# alpha_board_05a.net
KiCad netlist of a schematic drawn in EAGLE
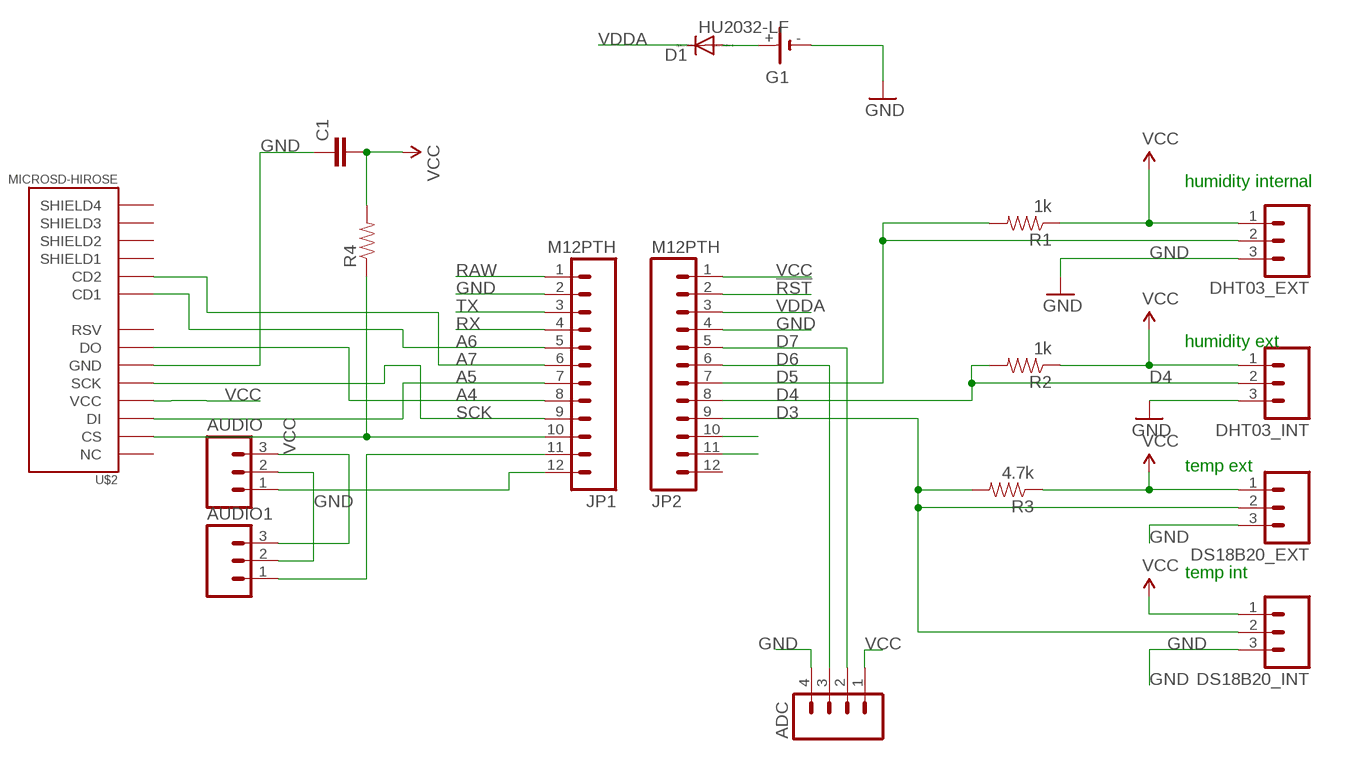
[diagram p0: schematic, sheet 1]

(export (version "E")
  (design (tool "Eeschema 10.0.6"))
  (components
    (comp (ref "ADC")
      (value "M04LOCK_LONGPADS")
      (footprint "eagle-import:1X04_LOCK_LONGPADS")
      (libsource (lib "eagle-import") (part "M04LOCK_LONGPADS"))
    )
    (comp (ref "AUDIO")
      (value "M03LOCK")
      (footprint "eagle-import:1X03_LOCK")
      (libsource (lib "eagle-import") (part "M03LOCK"))
    )
    (comp (ref "AUDIO1")
      (value "M03LOCK")
      (footprint "eagle-import:1X03_LOCK")
      (libsource (lib "eagle-import") (part "M03LOCK"))
    )
    (comp (ref "C1")
      (value "CAP1206")
      (footprint "eagle-import:1206")
      (libsource (lib "eagle-import") (part "CAP1206"))
    )
    (comp (ref "D1")
      (value "DIODE-SOD323-W")
      (footprint "eagle-import:SOD323-W")
      (libsource (lib "eagle-import") (part "DIODE-SOD323-W"))
    )
    (comp (ref "DHT03_EXT")
      (value "M03LOCK")
      (footprint "eagle-import:1X03_LOCK")
      (libsource (lib "eagle-import") (part "M03LOCK"))
    )
    (comp (ref "DHT03_INT")
      (value "M03LOCK")
      (footprint "eagle-import:1X03_LOCK")
      (libsource (lib "eagle-import") (part "M03LOCK"))
    )
    (comp (ref "DS18B20_EXT")
      (value "M03LOCK")
      (footprint "eagle-import:1X03_LOCK")
      (libsource (lib "eagle-import") (part "M03LOCK"))
    )
    (comp (ref "DS18B20_INT")
      (value "M03LOCK")
      (footprint "eagle-import:1X03_LOCK")
      (libsource (lib "eagle-import") (part "M03LOCK"))
    )
    (comp (ref "G1")
      (value "HU2032-LF")
      (footprint "eagle-import:HU2032-LF")
      (libsource (lib "eagle-import") (part "HU2032-LF"))
    )
    (comp (ref "JP1")
      (value "M12PTH")
      (footprint "eagle-import:1X12-SMALL-PADS")
      (libsource (lib "eagle-import") (part "M12PTH"))
    )
    (comp (ref "JP2")
      (value "M12PTH")
      (footprint "eagle-import:1X12-SMALL-PADS")
      (libsource (lib "eagle-import") (part "M12PTH"))
    )
    (comp (ref "R1")
      (value "1k")
      (footprint "eagle-import:1206")
      (libsource (lib "eagle-import") (part "RESISTOR1206"))
    )
    (comp (ref "R2")
      (value "1k")
      (footprint "eagle-import:1206")
      (libsource (lib "eagle-import") (part "RESISTOR1206"))
    )
    (comp (ref "R3")
      (value "4.7k")
      (footprint "eagle-import:1206")
      (libsource (lib "eagle-import") (part "RESISTOR1206"))
    )
    (comp (ref "R4")
      (value "RESISTOR1206")
      (footprint "eagle-import:1206")
      (libsource (lib "eagle-import") (part "RESISTOR1206"))
    )
    (comp (ref "U$2")
      (value "MICROSD-HIROSE")
      (footprint "eagle-import:MICROSD_HOLDER-HIROSE-DM3AT")
      (libsource (lib "eagle-import") (part "MICROSD-HIROSE"))
    )
  )
  (nets
    (net (code "1") (name "/A4") (class "Default")
      (node (ref "JP1") (pin "8") (pinfunction "8_8") (pintype "passive"))
      (node (ref "U$2") (pin "DAT0") (pinfunction "DO_DAT0") (pintype "bidirectional"))
    )
    (net (code "2") (name "/A5") (class "Default")
      (node (ref "JP1") (pin "7") (pinfunction "7_7") (pintype "passive"))
      (node (ref "U$2") (pin "CMD") (pinfunction "DI_CMD") (pintype "bidirectional"))
    )
    (net (code "3") (name "/A6") (class "Default")
      (node (ref "JP1") (pin "5") (pinfunction "5_5") (pintype "passive"))
      (node (ref "U$2") (pin "CD1") (pinfunction "CD1_CD1") (pintype "bidirectional"))
    )
    (net (code "4") (name "/A7") (class "Default")
      (node (ref "JP1") (pin "6") (pinfunction "6_6") (pintype "passive"))
      (node (ref "U$2") (pin "CD2") (pinfunction "CD2_CD2") (pintype "bidirectional"))
    )
    (net (code "5") (name "/D3") (class "Default")
      (node (ref "DS18B20_EXT") (pin "2") (pinfunction "2_2") (pintype "passive"))
      (node (ref "DS18B20_INT") (pin "2") (pinfunction "2_2") (pintype "passive"))
      (node (ref "JP2") (pin "9") (pinfunction "9_9") (pintype "passive"))
      (node (ref "R3") (pin "2") (pinfunction "2_2") (pintype "passive"))
    )
    (net (code "6") (name "/D4") (class "Default")
      (node (ref "DHT03_INT") (pin "2") (pinfunction "2_2") (pintype "passive"))
      (node (ref "JP2") (pin "8") (pinfunction "8_8") (pintype "passive"))
      (node (ref "R2") (pin "2") (pinfunction "2_2") (pintype "passive"))
    )
    (net (code "7") (name "/D5") (class "Default")
      (node (ref "DHT03_EXT") (pin "2") (pinfunction "2_2") (pintype "passive"))
      (node (ref "JP2") (pin "7") (pinfunction "7_7") (pintype "passive"))
      (node (ref "R1") (pin "2") (pinfunction "2_2") (pintype "passive"))
    )
    (net (code "8") (name "/D6") (class "Default")
      (node (ref "ADC") (pin "3") (pinfunction "3_3") (pintype "passive"))
      (node (ref "JP2") (pin "6") (pinfunction "6_6") (pintype "passive"))
    )
    (net (code "9") (name "/D7") (class "Default")
      (node (ref "ADC") (pin "2") (pinfunction "2_2") (pintype "passive"))
      (node (ref "JP2") (pin "5") (pinfunction "5_5") (pintype "passive"))
    )
    (net (code "10") (name "/RAW") (class "Default")
      (node (ref "JP1") (pin "1") (pinfunction "1_1") (pintype "passive"))
    )
    (net (code "11") (name "/RX") (class "Default")
      (node (ref "JP1") (pin "4") (pinfunction "4_4") (pintype "passive"))
    )
    (net (code "12") (name "/SCK") (class "Default")
      (node (ref "JP1") (pin "9") (pinfunction "9_9") (pintype "passive"))
      (node (ref "U$2") (pin "CLK") (pinfunction "SCK_CLK") (pintype "bidirectional"))
    )
    (net (code "13") (name "/TX") (class "Default")
      (node (ref "JP1") (pin "3") (pinfunction "3_3") (pintype "passive"))
    )
    (net (code "14") (name "/VDDA") (class "Default")
      (node (ref "D1") (pin "C") (pinfunction "C_C") (pintype "passive"))
      (node (ref "JP2") (pin "3") (pinfunction "3_3") (pintype "passive"))
    )
    (net (code "15") (name "/~{RST}") (class "Default")
      (node (ref "JP2") (pin "2") (pinfunction "2_2") (pintype "passive"))
    )
    (net (code "16") (name "GND") (class "Default")
      (node (ref "ADC") (pin "4") (pinfunction "4_4") (pintype "passive"))
      (node (ref "AUDIO") (pin "2") (pinfunction "2_2") (pintype "passive"))
      (node (ref "AUDIO1") (pin "2") (pinfunction "2_2") (pintype "passive"))
      (node (ref "C1") (pin "1") (pinfunction "1_1") (pintype "passive"))
      (node (ref "DHT03_EXT") (pin "3") (pinfunction "3_3") (pintype "passive"))
      (node (ref "DHT03_INT") (pin "3") (pinfunction "3_3") (pintype "passive"))
      (node (ref "DS18B20_EXT") (pin "3") (pinfunction "3_3") (pintype "passive"))
      (node (ref "DS18B20_INT") (pin "3") (pinfunction "3_3") (pintype "passive"))
      (node (ref "G1") (pin "-") (pinfunction "-_-") (pintype "passive"))
      (node (ref "JP1") (pin "2") (pinfunction "2_2") (pintype "passive"))
      (node (ref "JP2") (pin "4") (pinfunction "4_4") (pintype "passive"))
      (node (ref "U$2") (pin "VSS") (pinfunction "GND_VSS") (pintype "power_in"))
    )
    (net (code "17") (name "Net-(AUDIO-Pad1)") (class "Default")
      (node (ref "AUDIO") (pin "1") (pinfunction "1_1") (pintype "passive"))
      (node (ref "JP1") (pin "12") (pinfunction "12_12") (pintype "passive"))
    )
    (net (code "18") (name "Net-(AUDIO1-Pad1)") (class "Default")
      (node (ref "AUDIO1") (pin "1") (pinfunction "1_1") (pintype "passive"))
      (node (ref "JP1") (pin "11") (pinfunction "11_11") (pintype "passive"))
    )
    (net (code "19") (name "Net-(D1-PadA)") (class "Default")
      (node (ref "D1") (pin "A") (pinfunction "A_A") (pintype "passive"))
      (node (ref "G1") (pin "+") (pinfunction "+_+") (pintype "passive"))
    )
    (net (code "20") (name "Net-(U$2-CS)") (class "Default")
      (node (ref "JP1") (pin "10") (pinfunction "10_10") (pintype "passive"))
      (node (ref "R4") (pin "1") (pinfunction "1_1") (pintype "passive"))
      (node (ref "U$2") (pin "DAT3") (pinfunction "CS_DAT3") (pintype "bidirectional"))
    )
    (net (code "21") (name "VCC") (class "Default")
      (node (ref "ADC") (pin "1") (pinfunction "1_1") (pintype "passive"))
      (node (ref "AUDIO") (pin "3") (pinfunction "3_3") (pintype "passive"))
      (node (ref "AUDIO1") (pin "3") (pinfunction "3_3") (pintype "passive"))
      (node (ref "C1") (pin "2") (pinfunction "2_2") (pintype "passive"))
      (node (ref "DHT03_EXT") (pin "1") (pinfunction "1_1") (pintype "passive"))
      (node (ref "DHT03_INT") (pin "1") (pinfunction "1_1") (pintype "passive"))
      (node (ref "DS18B20_EXT") (pin "1") (pinfunction "1_1") (pintype "passive"))
      (node (ref "DS18B20_INT") (pin "1") (pinfunction "1_1") (pintype "passive"))
      (node (ref "JP2") (pin "1") (pinfunction "1_1") (pintype "passive"))
      (node (ref "R1") (pin "1") (pinfunction "1_1") (pintype "passive"))
      (node (ref "R2") (pin "1") (pinfunction "1_1") (pintype "passive"))
      (node (ref "R3") (pin "1") (pinfunction "1_1") (pintype "passive"))
      (node (ref "R4") (pin "2") (pinfunction "2_2") (pintype "passive"))
      (node (ref "U$2") (pin "VDD") (pinfunction "VCC_VDD") (pintype "power_in"))
    )
    (net (code "22") (name "unconnected-(G1-+-Pad+@1)") (class "Default")
      (node (ref "G1") (pin "+@1") (pinfunction "+_+@1") (pintype "passive"))
    )
    (net (code "23") (name "unconnected-(JP2-Pad10)") (class "Default")
      (node (ref "JP2") (pin "10") (pinfunction "10_10") (pintype "passive"))
    )
    (net (code "24") (name "unconnected-(JP2-Pad11)") (class "Default")
      (node (ref "JP2") (pin "11") (pinfunction "11_11") (pintype "passive"))
    )
    (net (code "25") (name "unconnected-(JP2-Pad12)") (class "Default")
      (node (ref "JP2") (pin "12") (pinfunction "12_12") (pintype "passive"))
    )
    (net (code "26") (name "unconnected-(U$2-NC-PadDAT2)") (class "Default")
      (node (ref "U$2") (pin "DAT2") (pinfunction "NC_DAT2") (pintype "bidirectional"))
    )
    (net (code "27") (name "unconnected-(U$2-RSV-PadDAT1)") (class "Default")
      (node (ref "U$2") (pin "DAT1") (pinfunction "RSV_DAT1") (pintype "bidirectional"))
    )
    (net (code "28") (name "unconnected-(U$2-SHIELD1-PadBODY1)") (class "Default")
      (node (ref "U$2") (pin "BODY1") (pinfunction "SHIELD1_BODY1") (pintype "bidirectional"))
    )
    (net (code "29") (name "unconnected-(U$2-SHIELD2-PadBODY2)") (class "Default")
      (node (ref "U$2") (pin "BODY2") (pinfunction "SHIELD2_BODY2") (pintype "bidirectional"))
    )
    (net (code "30") (name "unconnected-(U$2-SHIELD3-PadBODY3)") (class "Default")
      (node (ref "U$2") (pin "BODY3") (pinfunction "SHIELD3_BODY3") (pintype "bidirectional"))
    )
    (net (code "31") (name "unconnected-(U$2-SHIELD4-PadBODY4)") (class "Default")
      (node (ref "U$2") (pin "BODY4") (pinfunction "SHIELD4_BODY4") (pintype "bidirectional"))
    )
  )
)
